# AD8307_Add_on_v3.net
KiCad netlist of a schematic drawn in Altium Designer
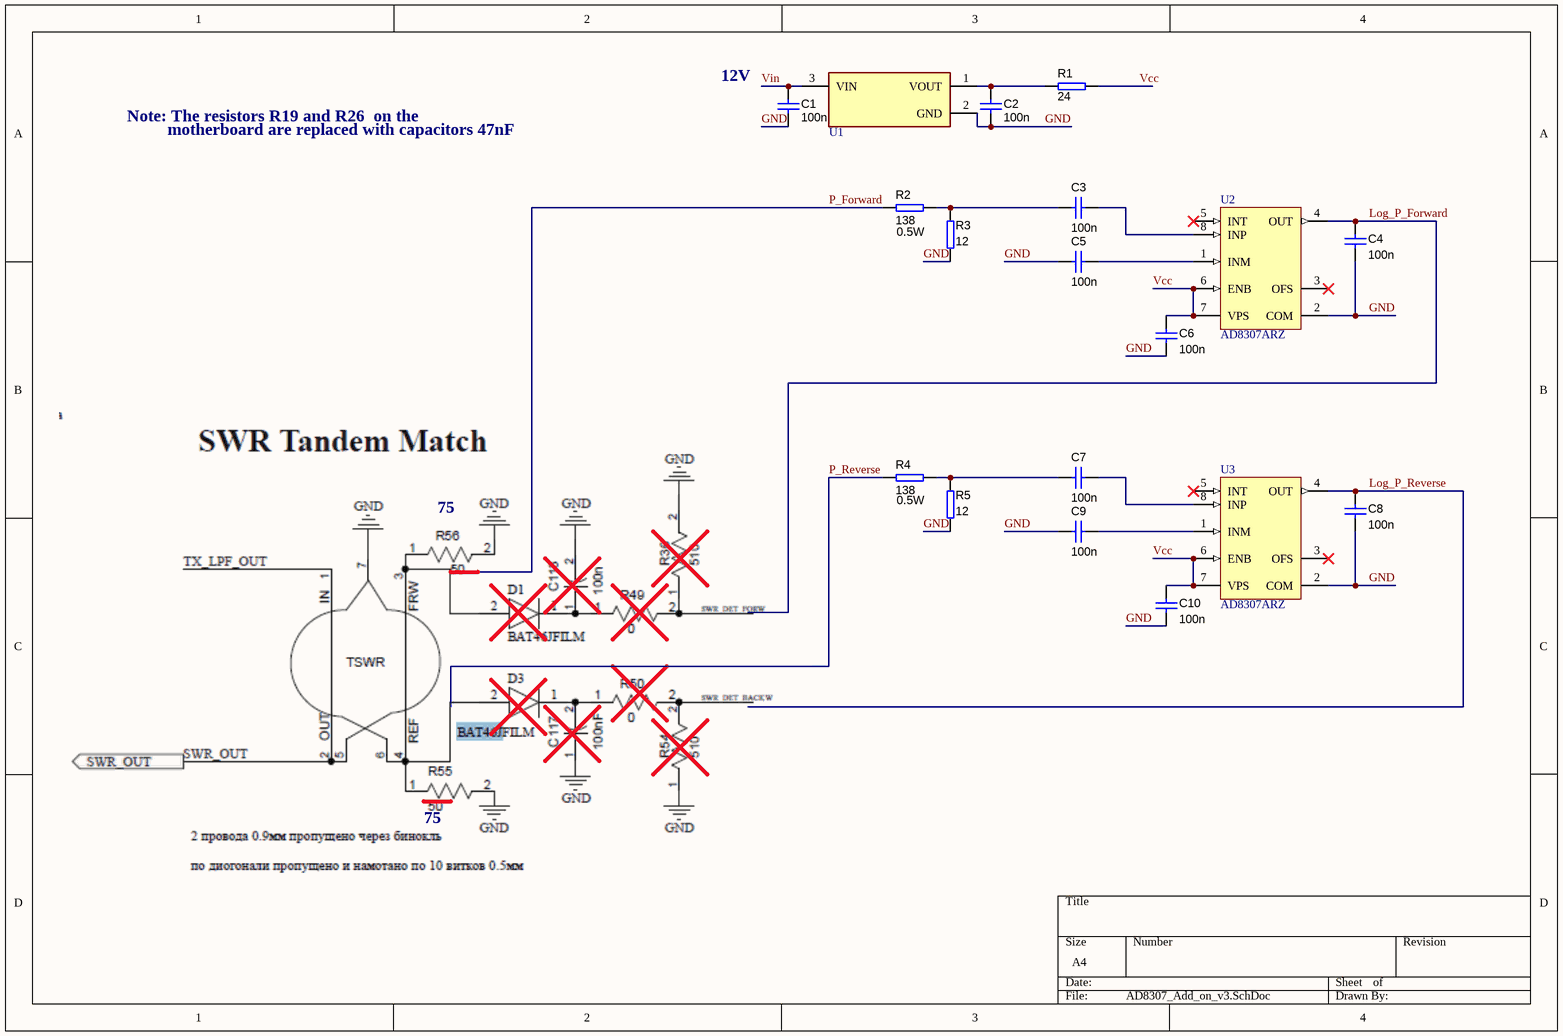
[diagram p0: AD8307_Add_on_v3.SchDoc]

(export (version "E")
  (design (tool "Eeschema 10.0.6"))
  (components
    (comp (ref "C1")
      (value "100n")
      (footprint "0805_HV")
      (description "CAP, CERM, +/- 10%, X7S,  0805")
      (libsource (lib "PSFB_v1") (part "C0805"))
    )
    (comp (ref "C2")
      (value "100n")
      (footprint "0805_HV")
      (description "CAP, CERM, +/- 10%, X7S,  0805")
      (libsource (lib "PSFB_v1") (part "C0805"))
    )
    (comp (ref "C3")
      (value "100n")
      (footprint "0805_HV")
      (description "CAP, CERM, +/- 10%, X7S,  0805")
      (libsource (lib "PSFB_v1") (part "C0805"))
    )
    (comp (ref "C4")
      (value "100n")
      (footprint "0805_HV")
      (description "CAP, CERM, +/- 10%, X7S,  0805")
      (libsource (lib "PSFB_v1") (part "C0805"))
    )
    (comp (ref "C5")
      (value "100n")
      (footprint "0805_HV")
      (description "CAP, CERM, +/- 10%, X7S,  0805")
      (libsource (lib "PSFB_v1") (part "C0805"))
    )
    (comp (ref "C6")
      (value "100n")
      (footprint "0805_HV")
      (description "CAP, CERM, +/- 10%, X7S,  0805")
      (libsource (lib "PSFB_v1") (part "C0805"))
    )
    (comp (ref "C7")
      (value "100n")
      (footprint "0805_HV")
      (description "CAP, CERM, +/- 10%, X7S,  0805")
      (libsource (lib "PSFB_v1") (part "C0805"))
    )
    (comp (ref "C8")
      (value "100n")
      (footprint "0805_HV")
      (description "CAP, CERM, +/- 10%, X7S,  0805")
      (libsource (lib "PSFB_v1") (part "C0805"))
    )
    (comp (ref "C9")
      (value "100n")
      (footprint "0805_HV")
      (description "CAP, CERM, +/- 10%, X7S,  0805")
      (libsource (lib "PSFB_v1") (part "C0805"))
    )
    (comp (ref "C10")
      (value "100n")
      (footprint "0805_HV")
      (description "CAP, CERM, +/- 10%, X7S,  0805")
      (libsource (lib "PSFB_v1") (part "C0805"))
    )
    (comp (ref "R1")
      (value "24")
      (footprint "0805_HV")
      (description "RES, 1%, 0.1 W, 0805")
      (libsource (lib "PSFB_v1") (part "R0805"))
    )
    (comp (ref "R2")
      (value "138")
      (footprint "1206")
      (description "RES, 1%, 0.5 W, 1206")
      (fields (field (name "VALUE2") "0.5W"))
      (libsource (lib "PSFB_v1") (part "R1206"))
    )
    (comp (ref "R3")
      (value "12")
      (footprint "0805_HV")
      (description "RES, 1%, 0.1 W, 0805")
      (libsource (lib "PSFB_v1") (part "R0805"))
    )
    (comp (ref "R4")
      (value "138")
      (footprint "1206")
      (description "RES, 1%, 0.5 W, 1206")
      (fields (field (name "VALUE2") "0.5W"))
      (libsource (lib "PSFB_v1") (part "R1206"))
    )
    (comp (ref "R5")
      (value "12")
      (footprint "0805_HV")
      (description "RES, 1%, 0.1 W, 0805")
      (libsource (lib "PSFB_v1") (part "R0805"))
    )
    (comp (ref "U1")
      (value "L78L05ACUTR")
      (footprint "STMicroelectronics_SOT-89-7098166_MFG")
      (libsource (lib "IC_STMicroelectronics_L78L05ACUTR_eec") (part "L78L05ACUTR"))
    )
    (comp (ref "U2")
      (value "AD8307ARZ")
      (footprint "ADI-R-8_M")
      (description "Low Cost, DC to 500 MHz, 92 dB Logarithmic Amplifier, 400ns Response Time, R-8, Pb-Free, 98 Tube")
      (libsource (lib "PSFB_v1") (part "AD8307ARZ"))
    )
    (comp (ref "U3")
      (value "AD8307ARZ")
      (footprint "ADI-R-8_M")
      (description "Low Cost, DC to 500 MHz, 92 dB Logarithmic Amplifier, 400ns Response Time, R-8, Pb-Free, 98 Tube")
      (libsource (lib "PSFB_v1") (part "AD8307ARZ"))
    )
  )
  (nets
    (net (code "1") (name "/GND") (class "Default")
      (node (ref "C1") (pin "2") (pinfunction "2_2") (pintype "passive"))
      (node (ref "C10") (pin "2") (pinfunction "2_2") (pintype "passive"))
      (node (ref "C2") (pin "2") (pinfunction "2_2") (pintype "passive"))
      (node (ref "C4") (pin "2") (pinfunction "2_2") (pintype "passive"))
      (node (ref "C5") (pin "2") (pinfunction "2_2") (pintype "passive"))
      (node (ref "C6") (pin "2") (pinfunction "2_2") (pintype "passive"))
      (node (ref "C8") (pin "2") (pinfunction "2_2") (pintype "passive"))
      (node (ref "C9") (pin "2") (pinfunction "2_2") (pintype "passive"))
      (node (ref "R3") (pin "1") (pinfunction "1_1") (pintype "passive"))
      (node (ref "R5") (pin "1") (pinfunction "1_1") (pintype "passive"))
      (node (ref "U1") (pin "2") (pinfunction "GND_2") (pintype "power_in"))
      (node (ref "U2") (pin "2") (pinfunction "COM_2") (pintype "power_in"))
      (node (ref "U3") (pin "2") (pinfunction "COM_2") (pintype "power_in"))
    )
    (net (code "2") (name "/Log_P_Forward") (class "Default")
      (node (ref "C4") (pin "1") (pinfunction "1_1") (pintype "passive"))
      (node (ref "U2") (pin "4") (pinfunction "OUT_4") (pintype "output"))
    )
    (net (code "3") (name "/Log_P_Reverse") (class "Default")
      (node (ref "C8") (pin "1") (pinfunction "1_1") (pintype "passive"))
      (node (ref "U3") (pin "4") (pinfunction "OUT_4") (pintype "output"))
    )
    (net (code "4") (name "/P_Forward") (class "Default")
      (node (ref "R2") (pin "1") (pinfunction "1_1") (pintype "passive"))
    )
    (net (code "5") (name "/P_Reverse") (class "Default")
      (node (ref "R4") (pin "1") (pinfunction "1_1") (pintype "passive"))
    )
    (net (code "6") (name "/Vcc") (class "Default")
      (node (ref "C10") (pin "1") (pinfunction "1_1") (pintype "passive"))
      (node (ref "C6") (pin "1") (pinfunction "1_1") (pintype "passive"))
      (node (ref "R1") (pin "1") (pinfunction "1_1") (pintype "passive"))
      (node (ref "U2") (pin "6") (pinfunction "ENB_6") (pintype "input"))
      (node (ref "U2") (pin "7") (pinfunction "VPS_7") (pintype "power_in"))
      (node (ref "U3") (pin "6") (pinfunction "ENB_6") (pintype "input"))
      (node (ref "U3") (pin "7") (pinfunction "VPS_7") (pintype "power_in"))
    )
    (net (code "7") (name "/Vin") (class "Default")
      (node (ref "C1") (pin "1") (pinfunction "1_1") (pintype "passive"))
      (node (ref "U1") (pin "3") (pinfunction "VIN_3") (pintype "power_in"))
    )
    (net (code "8") (name "Net-(C3-Pad2)") (class "Default")
      (node (ref "C3") (pin "2") (pinfunction "2_2") (pintype "passive"))
      (node (ref "R2") (pin "2") (pinfunction "2_2") (pintype "passive"))
      (node (ref "R3") (pin "2") (pinfunction "2_2") (pintype "passive"))
    )
    (net (code "9") (name "Net-(C7-Pad2)") (class "Default")
      (node (ref "C7") (pin "2") (pinfunction "2_2") (pintype "passive"))
      (node (ref "R4") (pin "2") (pinfunction "2_2") (pintype "passive"))
      (node (ref "R5") (pin "2") (pinfunction "2_2") (pintype "passive"))
    )
    (net (code "10") (name "Net-(U1-VOUT)") (class "Default")
      (node (ref "C2") (pin "1") (pinfunction "1_1") (pintype "passive"))
      (node (ref "R1") (pin "2") (pinfunction "2_2") (pintype "passive"))
      (node (ref "U1") (pin "1") (pinfunction "VOUT_1") (pintype "power_in"))
    )
    (net (code "11") (name "Net-(U2-INM)") (class "Default")
      (node (ref "C5") (pin "1") (pinfunction "1_1") (pintype "passive"))
      (node (ref "U2") (pin "1") (pinfunction "INM_1") (pintype "input"))
    )
    (net (code "12") (name "Net-(U2-INP)") (class "Default")
      (node (ref "C3") (pin "1") (pinfunction "1_1") (pintype "passive"))
      (node (ref "U2") (pin "8") (pinfunction "INP_8") (pintype "input"))
    )
    (net (code "13") (name "Net-(U3-INM)") (class "Default")
      (node (ref "C9") (pin "1") (pinfunction "1_1") (pintype "passive"))
      (node (ref "U3") (pin "1") (pinfunction "INM_1") (pintype "input"))
    )
    (net (code "14") (name "Net-(U3-INP)") (class "Default")
      (node (ref "C7") (pin "1") (pinfunction "1_1") (pintype "passive"))
      (node (ref "U3") (pin "8") (pinfunction "INP_8") (pintype "input"))
    )
    (net (code "15") (name "unconnected-(U2-INT-Pad5)") (class "Default")
      (node (ref "U2") (pin "5") (pinfunction "INT_5") (pintype "input+no_connect"))
    )
    (net (code "16") (name "unconnected-(U2-OFS-Pad3)") (class "Default")
      (node (ref "U2") (pin "3") (pinfunction "OFS_3") (pintype "passive+no_connect"))
    )
    (net (code "17") (name "unconnected-(U3-INT-Pad5)") (class "Default")
      (node (ref "U3") (pin "5") (pinfunction "INT_5") (pintype "input+no_connect"))
    )
    (net (code "18") (name "unconnected-(U3-OFS-Pad3)") (class "Default")
      (node (ref "U3") (pin "3") (pinfunction "OFS_3") (pintype "passive+no_connect"))
    )
  )
)
